# TopSheet.net
KiCad netlist of a schematic drawn in Altium Designer
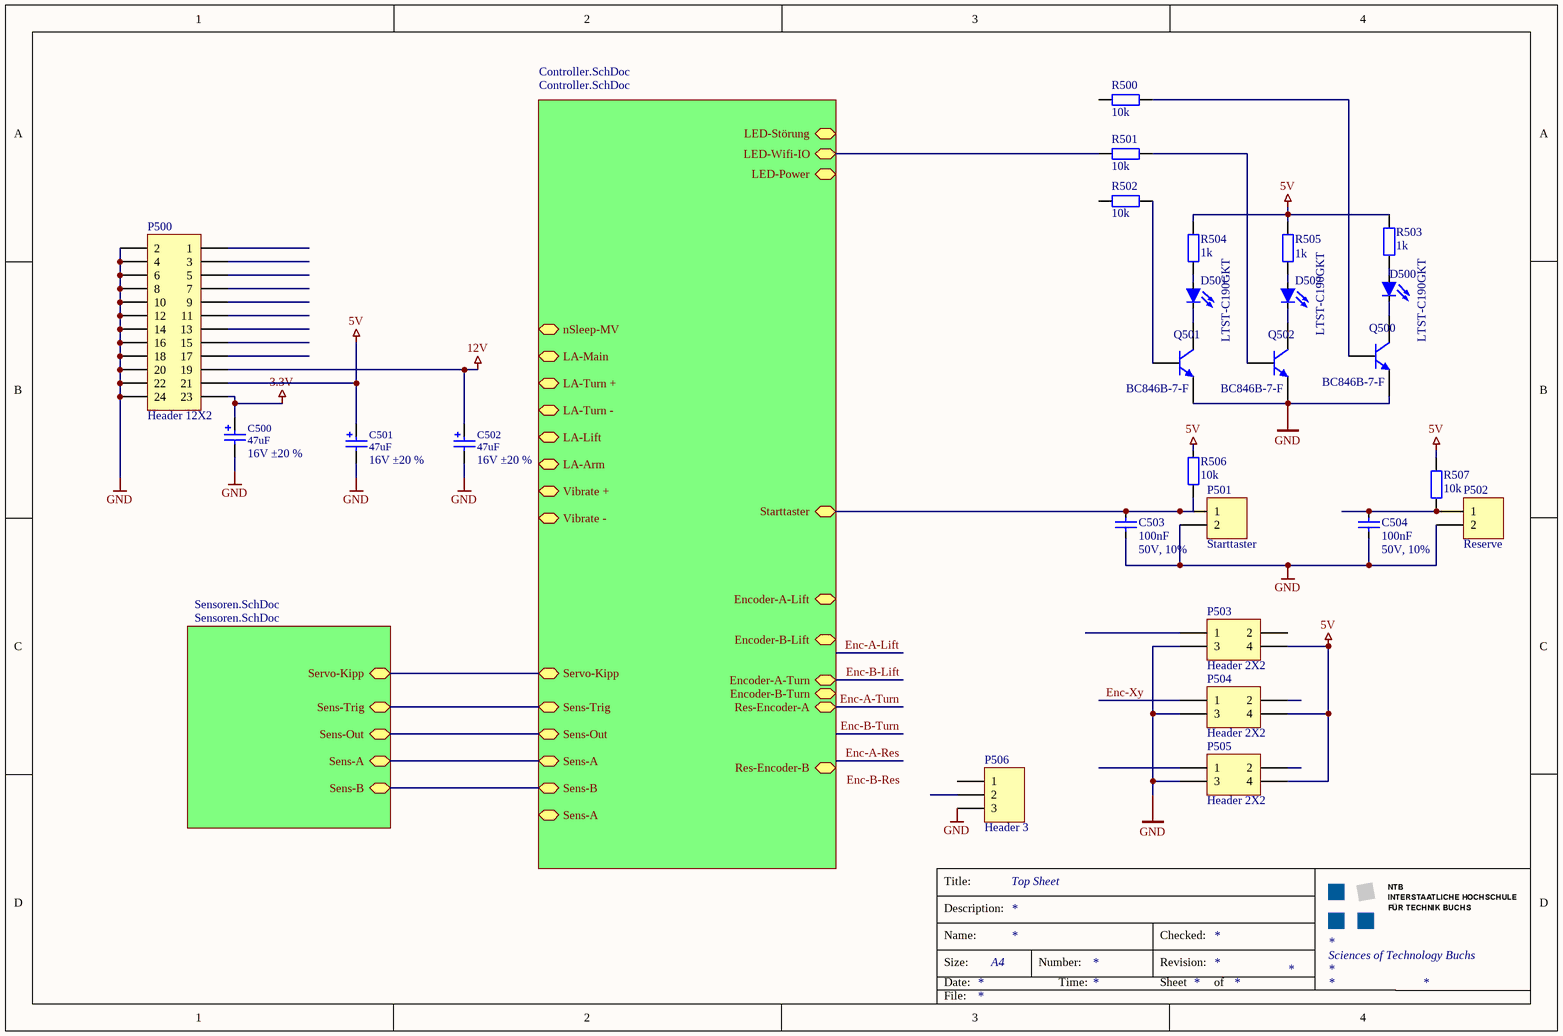
[diagram p0: TopSheet.schdoc]

(export (version "E")
  (design (tool "Eeschema 10.0.6"))
  (components
    (comp (ref "C500")
      (value "47uF")
      (footprint "CDE_CAP AVE CODE D_H")
      (description "ELKO, 47uF, 16V, CDE_AVE476M16D16T-F_AVE CODE D")
      (fields
        (field (name "MANUFACTURER") "Cornell Dubilier")
        (field (name "VALUEADDON") "16V ±20 %")
        (field (name "Comment") "AVE476M16D16T-F")
        (field (name "PUBLISHER") "Stefan Ursella, M.Eng")
      )
      (libsource (lib "IR-Sensor") (part "ELKO 47uF 16V"))
    )
    (comp (ref "C501")
      (value "47uF")
      (footprint "CDE_CAP AVE CODE D_H")
      (description "ELKO, 47uF, 16V, CDE_AVE476M16D16T-F_AVE CODE D")
      (fields
        (field (name "MANUFACTURER") "Cornell Dubilier")
        (field (name "VALUEADDON") "16V ±20 %")
        (field (name "Comment") "AVE476M16D16T-F")
        (field (name "PUBLISHER") "Stefan Ursella, M.Eng")
      )
      (libsource (lib "IR-Sensor") (part "ELKO 47uF 16V"))
    )
    (comp (ref "C502")
      (value "47uF")
      (footprint "CDE_CAP AVE CODE D_H")
      (description "ELKO, 47uF, 16V, CDE_AVE476M16D16T-F_AVE CODE D")
      (fields
        (field (name "MANUFACTURER") "Cornell Dubilier")
        (field (name "VALUEADDON") "16V ±20 %")
        (field (name "Comment") "AVE476M16D16T-F")
        (field (name "PUBLISHER") "Stefan Ursella, M.Eng")
      )
      (libsource (lib "IR-Sensor") (part "ELKO 47uF 16V"))
    )
    (comp (ref "C503")
      (value "100nF")
      (footprint "CAP-0805[2012]")
      (description "100n 50V X7R MLCC 0805 (1608 Metric)")
      (fields (field (name "TOLERANCE") "10%") (field (name "VALADDON") "50V, 10%"))
      (libsource (lib "IR-Sensor") (part "MLCC 0805 100n 50V"))
    )
    (comp (ref "C504")
      (value "100nF")
      (footprint "CAP-0805[2012]")
      (description "100n 50V X7R MLCC 0805 (1608 Metric)")
      (fields (field (name "TOLERANCE") "10%") (field (name "VALADDON") "50V, 10%"))
      (libsource (lib "IR-Sensor") (part "MLCC 0805 100n 50V"))
    )
    (comp (ref "D500")
      (value "LTST-C190GKT")
      (footprint "LED 0603 green")
      (description "LED SMD 0603 green 6mcd")
      (libsource (lib "IR-Sensor") (part "LED Green"))
    )
    (comp (ref "D501")
      (value "LTST-C190GKT")
      (footprint "LED 0603 green")
      (description "LED SMD 0603 green 6mcd")
      (libsource (lib "IR-Sensor") (part "LED Green"))
    )
    (comp (ref "D502")
      (value "LTST-C190GKT")
      (footprint "LED 0603 green")
      (description "LED SMD 0603 green 6mcd")
      (libsource (lib "IR-Sensor") (part "LED Green"))
    )
    (comp (ref "P500")
      (value "Header 12X2")
      (footprint "HDR2X12")
      (description "Header, 12-Pin, Dual row")
      (fields (field (name "PUBLISHER") "Altium Limited"))
      (libsource (lib "Miscellaneous Connectors") (part "Header 12X2"))
    )
    (comp (ref "P501")
      (value "Starttaster")
      (footprint "HDR1X2")
      (description "Header, 2-Pin")
      (fields (field (name "PUBLISHER") "Altium Limited"))
      (libsource (lib "Miscellaneous Connectors") (part "Header 2"))
    )
    (comp (ref "P502")
      (value "Reserve")
      (footprint "HDR1X2")
      (description "Header, 2-Pin")
      (fields (field (name "PUBLISHER") "Altium Limited"))
      (libsource (lib "Miscellaneous Connectors") (part "Header 2"))
    )
    (comp (ref "P503")
      (value "Header 2X2")
      (footprint "HDR2X2")
      (description "Header, 2-Pin, Dual row")
      (fields (field (name "PUBLISHER") "Altium Limited"))
      (libsource (lib "Miscellaneous Connectors") (part "Header 2X2"))
    )
    (comp (ref "P504")
      (value "Header 2X2")
      (footprint "HDR2X2")
      (description "Header, 2-Pin, Dual row")
      (fields (field (name "PUBLISHER") "Altium Limited"))
      (libsource (lib "Miscellaneous Connectors") (part "Header 2X2"))
    )
    (comp (ref "P505")
      (value "Header 2X2")
      (footprint "HDR2X2")
      (description "Header, 2-Pin, Dual row")
      (fields (field (name "PUBLISHER") "Altium Limited"))
      (libsource (lib "Miscellaneous Connectors") (part "Header 2X2"))
    )
    (comp (ref "P506")
      (value "Header 3")
      (footprint "HDR1X3")
      (description "Header, 3-Pin")
      (fields (field (name "PUBLISHER") "Altium Limited"))
      (libsource (lib "Miscellaneous Connectors") (part "Header 3"))
    )
    (comp (ref "Q500")
      (value "BC846B-7-F")
      (footprint "SOT-23")
      (description "NPN General-purpose Transistor")
      (fields (field (name "MANUFACTURER") "DIODES INC") (field (name "PUBLISHER") "Altium Limited"))
      (libsource (lib "IR-Sensor") (part "BC846B-SOT23"))
    )
    (comp (ref "Q501")
      (value "BC846B-7-F")
      (footprint "SOT-23")
      (description "NPN General-purpose Transistor")
      (fields (field (name "MANUFACTURER") "DIODES INC") (field (name "PUBLISHER") "Altium Limited"))
      (libsource (lib "IR-Sensor") (part "BC846B-SOT23"))
    )
    (comp (ref "Q502")
      (value "BC846B-7-F")
      (footprint "SOT-23")
      (description "NPN General-purpose Transistor")
      (fields (field (name "MANUFACTURER") "DIODES INC") (field (name "PUBLISHER") "Altium Limited"))
      (libsource (lib "IR-Sensor") (part "BC846B-SOT23"))
    )
    (comp (ref "R500")
      (value "10k")
      (footprint "RES-0805[2012]")
      (description "0805 (2013 Metric) 1/10 W 10K 1 Thick Film Chip Resistor")
      (fields (field (name "POWER") "1/10 W") (field (name "TOLERANCE") "1%"))
      (libsource (lib "IR-Sensor") (part "RES 0805"))
    )
    (comp (ref "R501")
      (value "10k")
      (footprint "RES-0805[2012]")
      (description "0805 (2013 Metric) 1/10 W 10K 1 Thick Film Chip Resistor")
      (fields (field (name "POWER") "1/10 W") (field (name "TOLERANCE") "1%"))
      (libsource (lib "IR-Sensor") (part "RES 0805"))
    )
    (comp (ref "R502")
      (value "10k")
      (footprint "RES-0805[2012]")
      (description "0805 (2013 Metric) 1/10 W 10K 1 Thick Film Chip Resistor")
      (fields (field (name "POWER") "1/10 W") (field (name "TOLERANCE") "1%"))
      (libsource (lib "IR-Sensor") (part "RES 0805"))
    )
    (comp (ref "R503")
      (value "1k")
      (footprint "RES-0805[2012]")
      (description "0805 (2013 Metric) 1/10 W 10K 1 Thick Film Chip Resistor")
      (fields (field (name "POWER") "1/10 W") (field (name "TOLERANCE") "1%"))
      (libsource (lib "IR-Sensor") (part "RES 0805"))
    )
    (comp (ref "R504")
      (value "1k")
      (footprint "RES-0805[2012]")
      (description "0805 (2013 Metric) 1/10 W 10K 1 Thick Film Chip Resistor")
      (fields (field (name "POWER") "1/10 W") (field (name "TOLERANCE") "1%"))
      (libsource (lib "IR-Sensor") (part "RES 0805"))
    )
    (comp (ref "R505")
      (value "1k")
      (footprint "RES-0805[2012]")
      (description "0805 (2013 Metric) 1/10 W 10K 1 Thick Film Chip Resistor")
      (fields (field (name "POWER") "1/10 W") (field (name "TOLERANCE") "1%"))
      (libsource (lib "IR-Sensor") (part "RES 0805"))
    )
    (comp (ref "R506")
      (value "10k")
      (footprint "RES-0805[2012]")
      (description "0805 (2013 Metric) 1/10 W 10K 1 Thick Film Chip Resistor")
      (fields (field (name "POWER") "1/10 W") (field (name "TOLERANCE") "1%"))
      (libsource (lib "IR-Sensor") (part "RES 0805"))
    )
    (comp (ref "R507")
      (value "10k")
      (footprint "RES-0805[2012]")
      (description "0805 (2013 Metric) 1/10 W 10K 1 Thick Film Chip Resistor")
      (fields (field (name "POWER") "1/10 W") (field (name "TOLERANCE") "1%"))
      (libsource (lib "IR-Sensor") (part "RES 0805"))
    )
  )
  (nets
    (net (code "7") (name "/Enc-Xy") (class "Default")
      (node (ref "P504") (pin "1") (pinfunction "1_1") (pintype "passive"))
    )
    (net (code "18") (name "/LED-Wifi-IO") (class "Default")
      (node (ref "R501") (pin "1") (pinfunction "1_1") (pintype "passive"))
    )
    (net (code "26") (name "/Starttaster") (class "Default")
      (node (ref "C503") (pin "2") (pinfunction "Neg_2") (pintype "passive"))
      (node (ref "P501") (pin "1") (pinfunction "1_1") (pintype "passive"))
      (node (ref "R506") (pin "1") (pinfunction "1_1") (pintype "passive"))
    )
    (net (code "30") (name "3.3V") (class "Default")
      (node (ref "C500") (pin "1") (pinfunction "Pos_1") (pintype "passive"))
      (node (ref "P500") (pin "23") (pinfunction "23_23") (pintype "passive"))
    )
    (net (code "31") (name "5V") (class "Default")
      (node (ref "C501") (pin "1") (pinfunction "Pos_1") (pintype "passive"))
      (node (ref "P500") (pin "21") (pinfunction "21_21") (pintype "passive"))
      (node (ref "P503") (pin "4") (pinfunction "4_4") (pintype "passive"))
      (node (ref "P504") (pin "4") (pinfunction "4_4") (pintype "passive"))
      (node (ref "P505") (pin "4") (pinfunction "4_4") (pintype "passive"))
      (node (ref "R503") (pin "2") (pinfunction "2_2") (pintype "passive"))
      (node (ref "R504") (pin "2") (pinfunction "2_2") (pintype "passive"))
      (node (ref "R505") (pin "2") (pinfunction "2_2") (pintype "passive"))
      (node (ref "R506") (pin "2") (pinfunction "2_2") (pintype "passive"))
      (node (ref "R507") (pin "2") (pinfunction "2_2") (pintype "passive"))
    )
    (net (code "32") (name "12V") (class "Default")
      (node (ref "C502") (pin "1") (pinfunction "Pos_1") (pintype "passive"))
      (node (ref "P500") (pin "19") (pinfunction "19_19") (pintype "passive"))
    )
    (net (code "33") (name "GND") (class "Default")
      (node (ref "C500") (pin "2") (pinfunction "Neg_2") (pintype "passive"))
      (node (ref "C501") (pin "2") (pinfunction "Neg_2") (pintype "passive"))
      (node (ref "C502") (pin "2") (pinfunction "Neg_2") (pintype "passive"))
      (node (ref "C503") (pin "1") (pinfunction "Pos_1") (pintype "passive"))
      (node (ref "C504") (pin "1") (pinfunction "Pos_1") (pintype "passive"))
      (node (ref "P500") (pin "10") (pinfunction "10_10") (pintype "passive"))
      (node (ref "P500") (pin "12") (pinfunction "12_12") (pintype "passive"))
      (node (ref "P500") (pin "14") (pinfunction "14_14") (pintype "passive"))
      (node (ref "P500") (pin "16") (pinfunction "16_16") (pintype "passive"))
      (node (ref "P500") (pin "18") (pinfunction "18_18") (pintype "passive"))
      (node (ref "P500") (pin "2") (pinfunction "2_2") (pintype "passive"))
      (node (ref "P500") (pin "20") (pinfunction "20_20") (pintype "passive"))
      (node (ref "P500") (pin "22") (pinfunction "22_22") (pintype "passive"))
      (node (ref "P500") (pin "24") (pinfunction "24_24") (pintype "passive"))
      (node (ref "P500") (pin "4") (pinfunction "4_4") (pintype "passive"))
      (node (ref "P500") (pin "6") (pinfunction "6_6") (pintype "passive"))
      (node (ref "P500") (pin "8") (pinfunction "8_8") (pintype "passive"))
      (node (ref "P501") (pin "2") (pinfunction "2_2") (pintype "passive"))
      (node (ref "P502") (pin "2") (pinfunction "2_2") (pintype "passive"))
      (node (ref "P503") (pin "3") (pinfunction "3_3") (pintype "passive"))
      (node (ref "P504") (pin "3") (pinfunction "3_3") (pintype "passive"))
      (node (ref "P505") (pin "3") (pinfunction "3_3") (pintype "passive"))
      (node (ref "P506") (pin "3") (pinfunction "3_3") (pintype "passive"))
      (node (ref "Q500") (pin "2") (pinfunction "E_2") (pintype "passive"))
      (node (ref "Q501") (pin "2") (pinfunction "E_2") (pintype "passive"))
      (node (ref "Q502") (pin "2") (pinfunction "E_2") (pintype "passive"))
    )
    (net (code "34") (name "Net-(C504-Neg)") (class "Default")
      (node (ref "C504") (pin "2") (pinfunction "Neg_2") (pintype "passive"))
      (node (ref "P502") (pin "1") (pinfunction "1_1") (pintype "passive"))
      (node (ref "R507") (pin "1") (pinfunction "1_1") (pintype "passive"))
    )
    (net (code "35") (name "Net-(D500-A)") (class "Default")
      (node (ref "D500") (pin "2") (pinfunction "A_2") (pintype "passive"))
      (node (ref "R503") (pin "1") (pinfunction "1_1") (pintype "passive"))
    )
    (net (code "36") (name "Net-(D500-K)") (class "Default")
      (node (ref "D500") (pin "1") (pinfunction "K_1") (pintype "passive"))
      (node (ref "Q500") (pin "3") (pinfunction "C_3") (pintype "passive"))
    )
    (net (code "37") (name "Net-(D501-A)") (class "Default")
      (node (ref "D501") (pin "2") (pinfunction "A_2") (pintype "passive"))
      (node (ref "R504") (pin "1") (pinfunction "1_1") (pintype "passive"))
    )
    (net (code "38") (name "Net-(D501-K)") (class "Default")
      (node (ref "D501") (pin "1") (pinfunction "K_1") (pintype "passive"))
      (node (ref "Q501") (pin "3") (pinfunction "C_3") (pintype "passive"))
    )
    (net (code "39") (name "Net-(D502-A)") (class "Default")
      (node (ref "D502") (pin "2") (pinfunction "A_2") (pintype "passive"))
      (node (ref "R505") (pin "1") (pinfunction "1_1") (pintype "passive"))
    )
    (net (code "40") (name "Net-(D502-K)") (class "Default")
      (node (ref "D502") (pin "1") (pinfunction "K_1") (pintype "passive"))
      (node (ref "Q502") (pin "3") (pinfunction "C_3") (pintype "passive"))
    )
    (net (code "41") (name "Net-(Q500-B)") (class "Default")
      (node (ref "Q500") (pin "1") (pinfunction "B_1") (pintype "passive"))
      (node (ref "R500") (pin "2") (pinfunction "2_2") (pintype "passive"))
    )
    (net (code "42") (name "Net-(Q501-B)") (class "Default")
      (node (ref "Q501") (pin "1") (pinfunction "B_1") (pintype "passive"))
      (node (ref "R502") (pin "2") (pinfunction "2_2") (pintype "passive"))
    )
    (net (code "43") (name "Net-(Q502-B)") (class "Default")
      (node (ref "Q502") (pin "1") (pinfunction "B_1") (pintype "passive"))
      (node (ref "R501") (pin "2") (pinfunction "2_2") (pintype "passive"))
    )
    (net (code "44") (name "unconnected-(P500-Pad1)") (class "Default")
      (node (ref "P500") (pin "1") (pinfunction "1_1") (pintype "passive"))
    )
    (net (code "45") (name "unconnected-(P500-Pad3)") (class "Default")
      (node (ref "P500") (pin "3") (pinfunction "3_3") (pintype "passive"))
    )
    (net (code "46") (name "unconnected-(P500-Pad5)") (class "Default")
      (node (ref "P500") (pin "5") (pinfunction "5_5") (pintype "passive"))
    )
    (net (code "47") (name "unconnected-(P500-Pad7)") (class "Default")
      (node (ref "P500") (pin "7") (pinfunction "7_7") (pintype "passive"))
    )
    (net (code "48") (name "unconnected-(P500-Pad9)") (class "Default")
      (node (ref "P500") (pin "9") (pinfunction "9_9") (pintype "passive"))
    )
    (net (code "49") (name "unconnected-(P500-Pad11)") (class "Default")
      (node (ref "P500") (pin "11") (pinfunction "11_11") (pintype "passive"))
    )
    (net (code "50") (name "unconnected-(P500-Pad13)") (class "Default")
      (node (ref "P500") (pin "13") (pinfunction "13_13") (pintype "passive"))
    )
    (net (code "51") (name "unconnected-(P500-Pad15)") (class "Default")
      (node (ref "P500") (pin "15") (pinfunction "15_15") (pintype "passive"))
    )
    (net (code "52") (name "unconnected-(P500-Pad17)") (class "Default")
      (node (ref "P500") (pin "17") (pinfunction "17_17") (pintype "passive"))
    )
    (net (code "53") (name "unconnected-(P503-Pad1)") (class "Default")
      (node (ref "P503") (pin "1") (pinfunction "1_1") (pintype "passive"))
    )
    (net (code "54") (name "unconnected-(P503-Pad2)") (class "Default")
      (node (ref "P503") (pin "2") (pinfunction "2_2") (pintype "passive"))
    )
    (net (code "55") (name "unconnected-(P504-Pad2)") (class "Default")
      (node (ref "P504") (pin "2") (pinfunction "2_2") (pintype "passive"))
    )
    (net (code "56") (name "unconnected-(P505-Pad1)") (class "Default")
      (node (ref "P505") (pin "1") (pinfunction "1_1") (pintype "passive"))
    )
    (net (code "57") (name "unconnected-(P505-Pad2)") (class "Default")
      (node (ref "P505") (pin "2") (pinfunction "2_2") (pintype "passive"))
    )
    (net (code "58") (name "unconnected-(P506-Pad1)") (class "Default")
      (node (ref "P506") (pin "1") (pinfunction "1_1") (pintype "passive"))
    )
    (net (code "59") (name "unconnected-(P506-Pad2)") (class "Default")
      (node (ref "P506") (pin "2") (pinfunction "2_2") (pintype "passive"))
    )
    (net (code "60") (name "unconnected-(R500-Pad1)") (class "Default")
      (node (ref "R500") (pin "1") (pinfunction "1_1") (pintype "passive"))
    )
    (net (code "61") (name "unconnected-(R502-Pad1)") (class "Default")
      (node (ref "R502") (pin "1") (pinfunction "1_1") (pintype "passive"))
    )
  )
)
